# ZynqPSDDR.net
KiCad netlist of a schematic drawn in Altium Designer
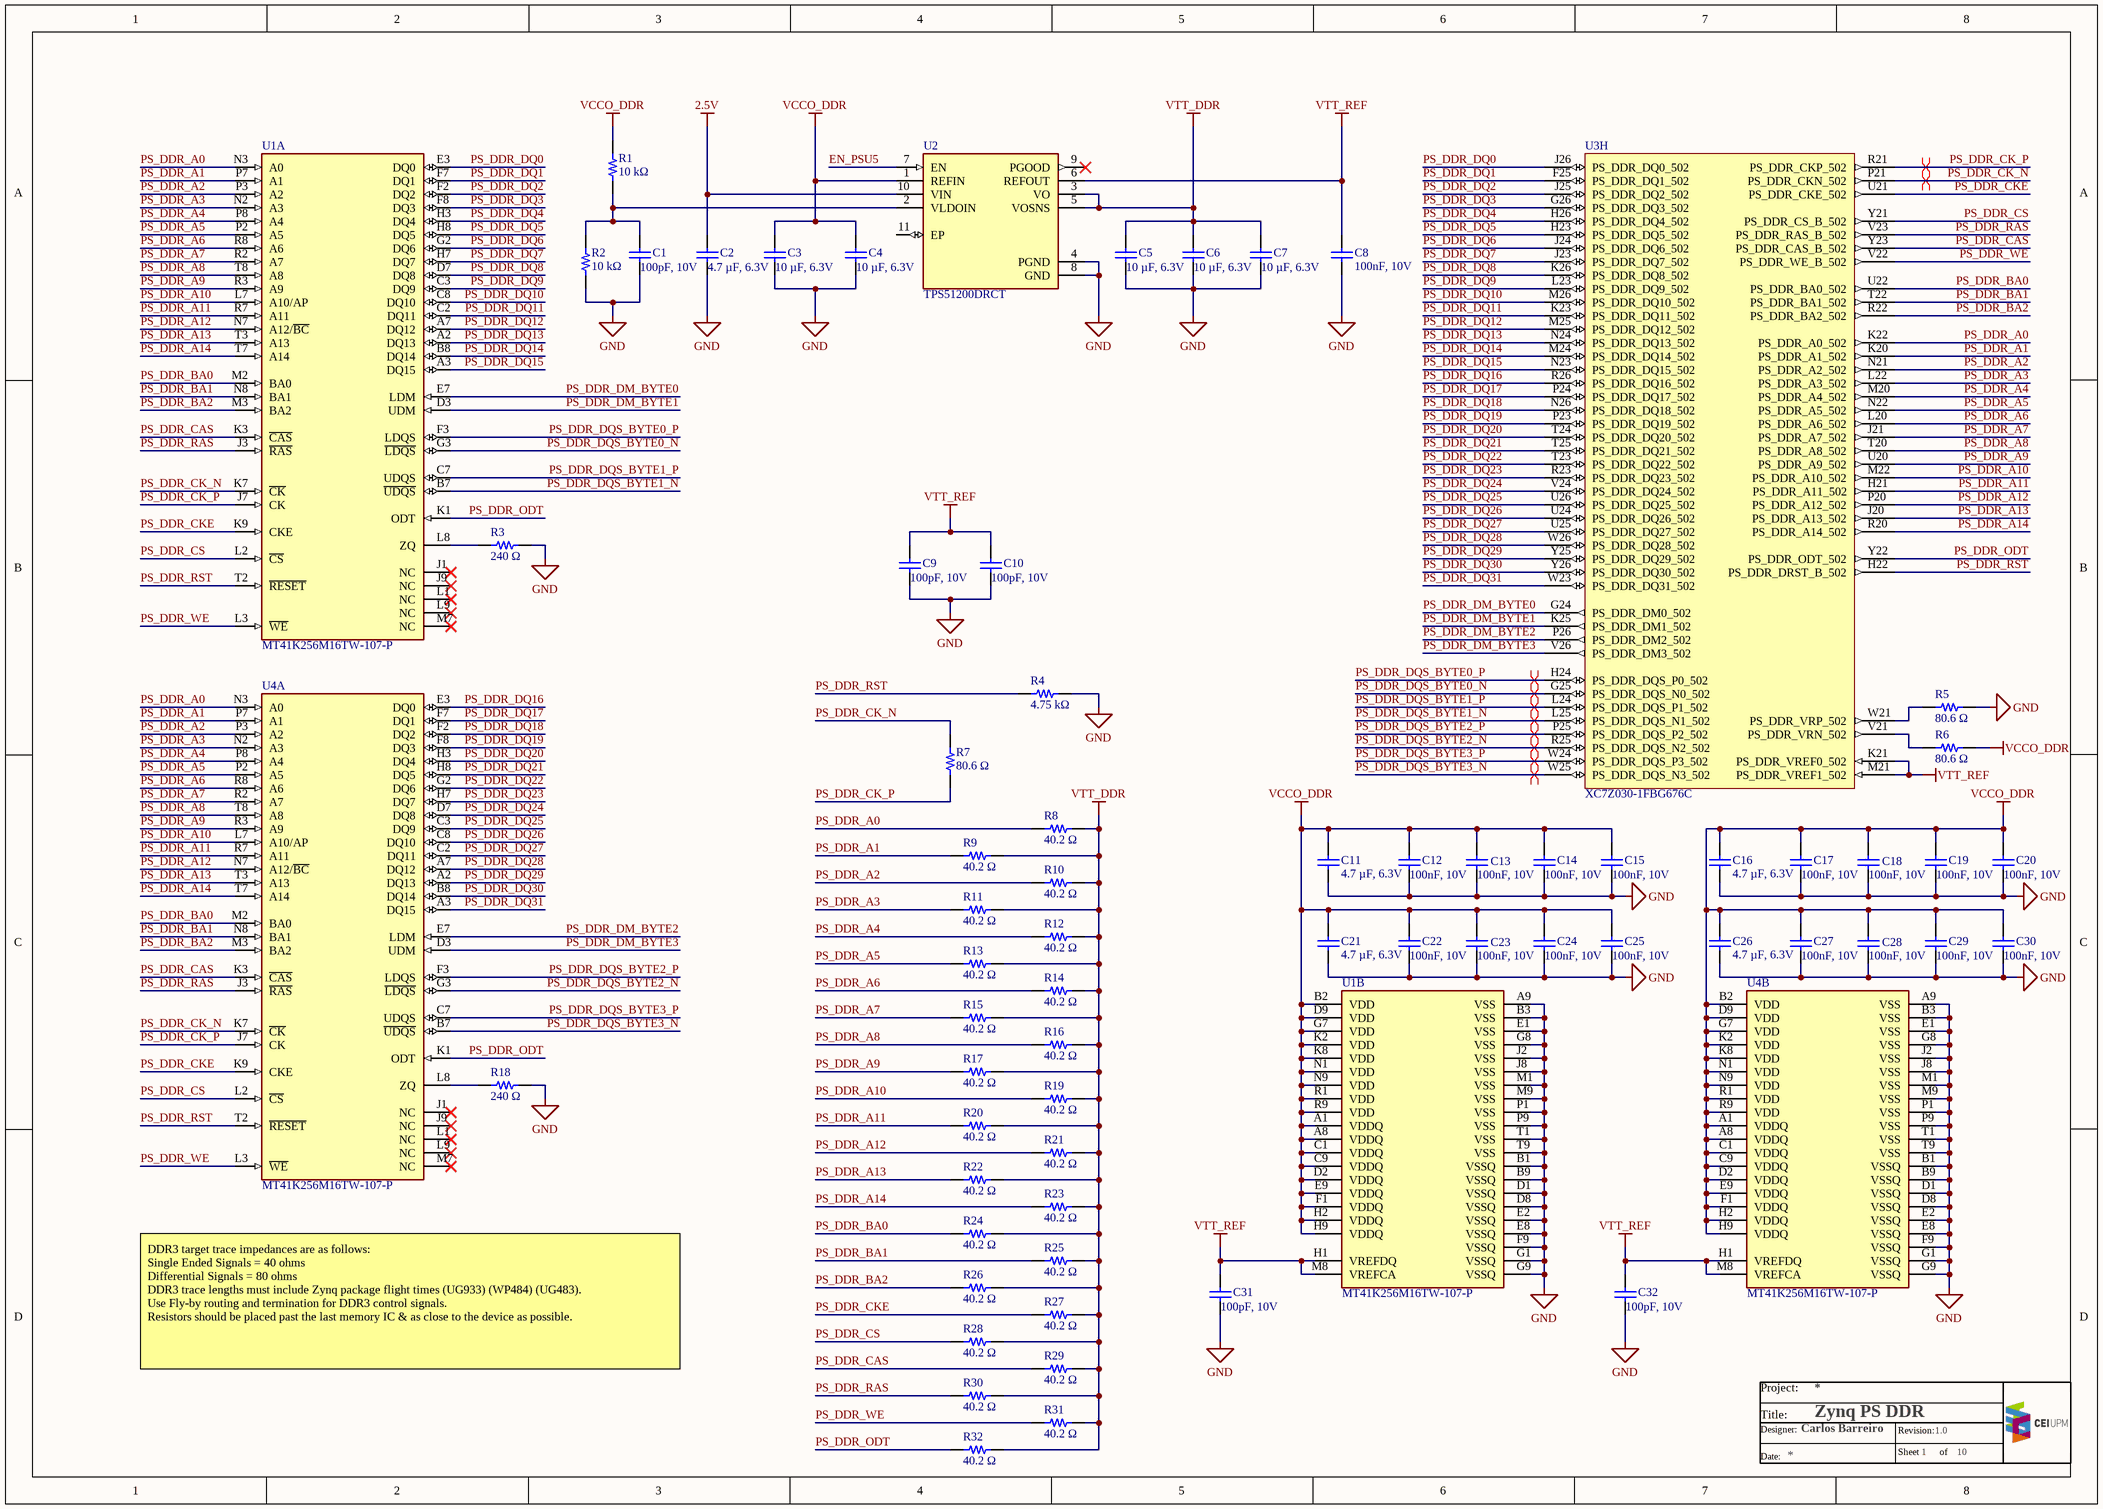
[diagram p0: ZynqPSDDR.SchDoc]

(export (version "E")
  (design (tool "Eeschema 10.0.6"))
  (components
    (comp (ref "C1")
      (value "100pF, 10V")
      (footprint "WURTH_WCAP-CSGP_0402")
      (description "WCAP-CSGP Multilayer Ceramic Chip Capacitor, General Purpose, size 0402, NP0, 100pF, 10V")
      (fields
        (field (name "MANUFACTURER PART NUMBER") "885012005013")
        (field (name "MANUFACTURER") "Wurth Elektronik")
      )
      (libsource (lib "SpaceVNXBaseBoard") (part "885012005013"))
    )
    (comp (ref "C2")
      (value "4.7 µF, 6.3V")
      (footprint "WURTH_WCAP-CSGP_0402")
      (description "Multilayer Ceramic Capacitors MLCC, size 0402, X5R, 4.7 µF, 6.3V")
      (fields
        (field (name "MANUFACTURER PART NUMBER") "GRM155C80J475MEAAD")
        (field (name "MANUFACTURER") "Murata")
      )
      (libsource (lib "SpaceVNXBaseBoard") (part "GRM155C80J475MEAAD"))
    )
    (comp (ref "C3")
      (value "10 µF, 6.3V")
      (footprint "WURTH_WCAP-CSGP_0402")
      (description "WCAP-CSGP Multilayer Ceramic Chip Capacitor, General Purpose, size 0402, X5R, 10uF, 6.3V")
      (fields
        (field (name "MANUFACTURER PART NUMBER") "885012105020")
        (field (name "MANUFACTURER") "Wurth Elektronik")
      )
      (libsource (lib "SpaceVNXBaseBoard") (part "885012105020"))
    )
    (comp (ref "C4")
      (value "10 µF, 6.3V")
      (footprint "WURTH_WCAP-CSGP_0402")
      (description "WCAP-CSGP Multilayer Ceramic Chip Capacitor, General Purpose, size 0402, X5R, 10uF, 6.3V")
      (fields
        (field (name "MANUFACTURER PART NUMBER") "885012105020")
        (field (name "MANUFACTURER") "Wurth Elektronik")
      )
      (libsource (lib "SpaceVNXBaseBoard") (part "885012105020"))
    )
    (comp (ref "C5")
      (value "10 µF, 6.3V")
      (footprint "WURTH_WCAP-CSGP_0402")
      (description "WCAP-CSGP Multilayer Ceramic Chip Capacitor, General Purpose, size 0402, X5R, 10uF, 6.3V")
      (fields
        (field (name "MANUFACTURER PART NUMBER") "885012105020")
        (field (name "MANUFACTURER") "Wurth Elektronik")
      )
      (libsource (lib "SpaceVNXBaseBoard") (part "885012105020"))
    )
    (comp (ref "C6")
      (value "10 µF, 6.3V")
      (footprint "WURTH_WCAP-CSGP_0402")
      (description "WCAP-CSGP Multilayer Ceramic Chip Capacitor, General Purpose, size 0402, X5R, 10uF, 6.3V")
      (fields
        (field (name "MANUFACTURER PART NUMBER") "885012105020")
        (field (name "MANUFACTURER") "Wurth Elektronik")
      )
      (libsource (lib "SpaceVNXBaseBoard") (part "885012105020"))
    )
    (comp (ref "C7")
      (value "10 µF, 6.3V")
      (footprint "WURTH_WCAP-CSGP_0402")
      (description "WCAP-CSGP Multilayer Ceramic Chip Capacitor, General Purpose, size 0402, X5R, 10uF, 6.3V")
      (fields
        (field (name "MANUFACTURER PART NUMBER") "885012105020")
        (field (name "MANUFACTURER") "Wurth Elektronik")
      )
      (libsource (lib "SpaceVNXBaseBoard") (part "885012105020"))
    )
    (comp (ref "C8")
      (value "100nF, 10V")
      (footprint "WURTH_WCAP-CSGP_0402")
      (description "WCAP-CSGP Multilayer Ceramic Chip Capacitor, General Purpose, size 0402, X7R, 100nF, 10V")
      (fields
        (field (name "MANUFACTURER PART NUMBER") "885012205018")
        (field (name "MANUFACTURER") "Wurth Elektronik")
      )
      (libsource (lib "SpaceVNXBaseBoard") (part "885012205018"))
    )
    (comp (ref "C9")
      (value "100pF, 10V")
      (footprint "WURTH_WCAP-CSGP_0402")
      (description "WCAP-CSGP Multilayer Ceramic Chip Capacitor, General Purpose, size 0402, NP0, 100pF, 10V")
      (fields
        (field (name "MANUFACTURER PART NUMBER") "885012005013")
        (field (name "MANUFACTURER") "Wurth Elektronik")
      )
      (libsource (lib "SpaceVNXBaseBoard") (part "885012005013"))
    )
    (comp (ref "C10")
      (value "100pF, 10V")
      (footprint "WURTH_WCAP-CSGP_0402")
      (description "WCAP-CSGP Multilayer Ceramic Chip Capacitor, General Purpose, size 0402, NP0, 100pF, 10V")
      (fields
        (field (name "MANUFACTURER PART NUMBER") "885012005013")
        (field (name "MANUFACTURER") "Wurth Elektronik")
      )
      (libsource (lib "SpaceVNXBaseBoard") (part "885012005013"))
    )
    (comp (ref "C11")
      (value "4.7 µF, 6.3V")
      (footprint "WURTH_WCAP-CSGP_0402")
      (description "Multilayer Ceramic Capacitors MLCC, size 0402, X5R, 4.7 µF, 6.3V")
      (fields
        (field (name "MANUFACTURER PART NUMBER") "GRM155C80J475MEAAD")
        (field (name "MANUFACTURER") "Murata")
      )
      (libsource (lib "SpaceVNXBaseBoard") (part "GRM155C80J475MEAAD"))
    )
    (comp (ref "C12")
      (value "100nF, 10V")
      (footprint "WURTH_WCAP-CSGP_0402")
      (description "WCAP-CSGP Multilayer Ceramic Chip Capacitor, General Purpose, size 0402, X7R, 100nF, 10V")
      (fields
        (field (name "MANUFACTURER PART NUMBER") "885012205018")
        (field (name "MANUFACTURER") "Wurth Elektronik")
      )
      (libsource (lib "SpaceVNXBaseBoard") (part "885012205018"))
    )
    (comp (ref "C13")
      (value "100nF, 10V")
      (footprint "WURTH_WCAP-CSGP_0402")
      (description "WCAP-CSGP Multilayer Ceramic Chip Capacitor, General Purpose, size 0402, X7R, 100nF, 10V")
      (fields
        (field (name "MANUFACTURER PART NUMBER") "885012205018")
        (field (name "MANUFACTURER") "Wurth Elektronik")
      )
      (libsource (lib "SpaceVNXBaseBoard") (part "885012205018"))
    )
    (comp (ref "C14")
      (value "100nF, 10V")
      (footprint "WURTH_WCAP-CSGP_0402")
      (description "WCAP-CSGP Multilayer Ceramic Chip Capacitor, General Purpose, size 0402, X7R, 100nF, 10V")
      (fields
        (field (name "MANUFACTURER PART NUMBER") "885012205018")
        (field (name "MANUFACTURER") "Wurth Elektronik")
      )
      (libsource (lib "SpaceVNXBaseBoard") (part "885012205018"))
    )
    (comp (ref "C15")
      (value "100nF, 10V")
      (footprint "WURTH_WCAP-CSGP_0402")
      (description "WCAP-CSGP Multilayer Ceramic Chip Capacitor, General Purpose, size 0402, X7R, 100nF, 10V")
      (fields
        (field (name "MANUFACTURER PART NUMBER") "885012205018")
        (field (name "MANUFACTURER") "Wurth Elektronik")
      )
      (libsource (lib "SpaceVNXBaseBoard") (part "885012205018"))
    )
    (comp (ref "C16")
      (value "4.7 µF, 6.3V")
      (footprint "WURTH_WCAP-CSGP_0402")
      (description "Multilayer Ceramic Capacitors MLCC, size 0402, X5R, 4.7 µF, 6.3V")
      (fields
        (field (name "MANUFACTURER PART NUMBER") "GRM155C80J475MEAAD")
        (field (name "MANUFACTURER") "Murata")
      )
      (libsource (lib "SpaceVNXBaseBoard") (part "GRM155C80J475MEAAD"))
    )
    (comp (ref "C17")
      (value "100nF, 10V")
      (footprint "WURTH_WCAP-CSGP_0402")
      (description "WCAP-CSGP Multilayer Ceramic Chip Capacitor, General Purpose, size 0402, X7R, 100nF, 10V")
      (fields
        (field (name "MANUFACTURER PART NUMBER") "885012205018")
        (field (name "MANUFACTURER") "Wurth Elektronik")
      )
      (libsource (lib "SpaceVNXBaseBoard") (part "885012205018"))
    )
    (comp (ref "C18")
      (value "100nF, 10V")
      (footprint "WURTH_WCAP-CSGP_0402")
      (description "WCAP-CSGP Multilayer Ceramic Chip Capacitor, General Purpose, size 0402, X7R, 100nF, 10V")
      (fields
        (field (name "MANUFACTURER PART NUMBER") "885012205018")
        (field (name "MANUFACTURER") "Wurth Elektronik")
      )
      (libsource (lib "SpaceVNXBaseBoard") (part "885012205018"))
    )
    (comp (ref "C19")
      (value "100nF, 10V")
      (footprint "WURTH_WCAP-CSGP_0402")
      (description "WCAP-CSGP Multilayer Ceramic Chip Capacitor, General Purpose, size 0402, X7R, 100nF, 10V")
      (fields
        (field (name "MANUFACTURER PART NUMBER") "885012205018")
        (field (name "MANUFACTURER") "Wurth Elektronik")
      )
      (libsource (lib "SpaceVNXBaseBoard") (part "885012205018"))
    )
    (comp (ref "C20")
      (value "100nF, 10V")
      (footprint "WURTH_WCAP-CSGP_0402")
      (description "WCAP-CSGP Multilayer Ceramic Chip Capacitor, General Purpose, size 0402, X7R, 100nF, 10V")
      (fields
        (field (name "MANUFACTURER PART NUMBER") "885012205018")
        (field (name "MANUFACTURER") "Wurth Elektronik")
      )
      (libsource (lib "SpaceVNXBaseBoard") (part "885012205018"))
    )
    (comp (ref "C21")
      (value "4.7 µF, 6.3V")
      (footprint "WURTH_WCAP-CSGP_0402")
      (description "Multilayer Ceramic Capacitors MLCC, size 0402, X5R, 4.7 µF, 6.3V")
      (fields
        (field (name "MANUFACTURER PART NUMBER") "GRM155C80J475MEAAD")
        (field (name "MANUFACTURER") "Murata")
      )
      (libsource (lib "SpaceVNXBaseBoard") (part "GRM155C80J475MEAAD"))
    )
    (comp (ref "C22")
      (value "100nF, 10V")
      (footprint "WURTH_WCAP-CSGP_0402")
      (description "WCAP-CSGP Multilayer Ceramic Chip Capacitor, General Purpose, size 0402, X7R, 100nF, 10V")
      (fields
        (field (name "MANUFACTURER PART NUMBER") "885012205018")
        (field (name "MANUFACTURER") "Wurth Elektronik")
      )
      (libsource (lib "SpaceVNXBaseBoard") (part "885012205018"))
    )
    (comp (ref "C23")
      (value "100nF, 10V")
      (footprint "WURTH_WCAP-CSGP_0402")
      (description "WCAP-CSGP Multilayer Ceramic Chip Capacitor, General Purpose, size 0402, X7R, 100nF, 10V")
      (fields
        (field (name "MANUFACTURER PART NUMBER") "885012205018")
        (field (name "MANUFACTURER") "Wurth Elektronik")
      )
      (libsource (lib "SpaceVNXBaseBoard") (part "885012205018"))
    )
    (comp (ref "C24")
      (value "100nF, 10V")
      (footprint "WURTH_WCAP-CSGP_0402")
      (description "WCAP-CSGP Multilayer Ceramic Chip Capacitor, General Purpose, size 0402, X7R, 100nF, 10V")
      (fields
        (field (name "MANUFACTURER PART NUMBER") "885012205018")
        (field (name "MANUFACTURER") "Wurth Elektronik")
      )
      (libsource (lib "SpaceVNXBaseBoard") (part "885012205018"))
    )
    (comp (ref "C25")
      (value "100nF, 10V")
      (footprint "WURTH_WCAP-CSGP_0402")
      (description "WCAP-CSGP Multilayer Ceramic Chip Capacitor, General Purpose, size 0402, X7R, 100nF, 10V")
      (fields
        (field (name "MANUFACTURER PART NUMBER") "885012205018")
        (field (name "MANUFACTURER") "Wurth Elektronik")
      )
      (libsource (lib "SpaceVNXBaseBoard") (part "885012205018"))
    )
    (comp (ref "C26")
      (value "4.7 µF, 6.3V")
      (footprint "WURTH_WCAP-CSGP_0402")
      (description "Multilayer Ceramic Capacitors MLCC, size 0402, X5R, 4.7 µF, 6.3V")
      (fields
        (field (name "MANUFACTURER PART NUMBER") "GRM155C80J475MEAAD")
        (field (name "MANUFACTURER") "Murata")
      )
      (libsource (lib "SpaceVNXBaseBoard") (part "GRM155C80J475MEAAD"))
    )
    (comp (ref "C27")
      (value "100nF, 10V")
      (footprint "WURTH_WCAP-CSGP_0402")
      (description "WCAP-CSGP Multilayer Ceramic Chip Capacitor, General Purpose, size 0402, X7R, 100nF, 10V")
      (fields
        (field (name "MANUFACTURER PART NUMBER") "885012205018")
        (field (name "MANUFACTURER") "Wurth Elektronik")
      )
      (libsource (lib "SpaceVNXBaseBoard") (part "885012205018"))
    )
    (comp (ref "C28")
      (value "100nF, 10V")
      (footprint "WURTH_WCAP-CSGP_0402")
      (description "WCAP-CSGP Multilayer Ceramic Chip Capacitor, General Purpose, size 0402, X7R, 100nF, 10V")
      (fields
        (field (name "MANUFACTURER PART NUMBER") "885012205018")
        (field (name "MANUFACTURER") "Wurth Elektronik")
      )
      (libsource (lib "SpaceVNXBaseBoard") (part "885012205018"))
    )
    (comp (ref "C29")
      (value "100nF, 10V")
      (footprint "WURTH_WCAP-CSGP_0402")
      (description "WCAP-CSGP Multilayer Ceramic Chip Capacitor, General Purpose, size 0402, X7R, 100nF, 10V")
      (fields
        (field (name "MANUFACTURER PART NUMBER") "885012205018")
        (field (name "MANUFACTURER") "Wurth Elektronik")
      )
      (libsource (lib "SpaceVNXBaseBoard") (part "885012205018"))
    )
    (comp (ref "C30")
      (value "100nF, 10V")
      (footprint "WURTH_WCAP-CSGP_0402")
      (description "WCAP-CSGP Multilayer Ceramic Chip Capacitor, General Purpose, size 0402, X7R, 100nF, 10V")
      (fields
        (field (name "MANUFACTURER PART NUMBER") "885012205018")
        (field (name "MANUFACTURER") "Wurth Elektronik")
      )
      (libsource (lib "SpaceVNXBaseBoard") (part "885012205018"))
    )
    (comp (ref "C31")
      (value "100pF, 10V")
      (footprint "WURTH_WCAP-CSGP_0402")
      (description "WCAP-CSGP Multilayer Ceramic Chip Capacitor, General Purpose, size 0402, NP0, 100pF, 10V")
      (fields
        (field (name "MANUFACTURER PART NUMBER") "885012005013")
        (field (name "MANUFACTURER") "Wurth Elektronik")
      )
      (libsource (lib "SpaceVNXBaseBoard") (part "885012005013"))
    )
    (comp (ref "C32")
      (value "100pF, 10V")
      (footprint "WURTH_WCAP-CSGP_0402")
      (description "WCAP-CSGP Multilayer Ceramic Chip Capacitor, General Purpose, size 0402, NP0, 100pF, 10V")
      (fields
        (field (name "MANUFACTURER PART NUMBER") "885012005013")
        (field (name "MANUFACTURER") "Wurth Elektronik")
      )
      (libsource (lib "SpaceVNXBaseBoard") (part "885012005013"))
    )
    (comp (ref "R1")
      (value "10 kΩ")
      (footprint "PANASONIC_ERJ2G_0402")
      (description "General Purpose Thick Film Chip Resistors")
      (fields (field (name "MANUFACTURER") "Panasonic"))
      (libsource (lib "SpaceVNXBaseBoard") (part "ERJ2RKF1002X"))
    )
    (comp (ref "R2")
      (value "10 kΩ")
      (footprint "PANASONIC_ERJ2G_0402")
      (description "General Purpose Thick Film Chip Resistors")
      (fields (field (name "MANUFACTURER") "Panasonic"))
      (libsource (lib "SpaceVNXBaseBoard") (part "ERJ2RKF1002X"))
    )
    (comp (ref "R3")
      (value "240 Ω")
      (footprint "PANASONIC_ERJ2G_0402")
      (description "General Purpose Thick Film Chip Resistors")
      (fields (field (name "MANUFACTURER") "Panasonic"))
      (libsource (lib "SpaceVNXBaseBoard") (part "ERJ2GEJ241X"))
    )
    (comp (ref "R4")
      (value "4.75 kΩ")
      (footprint "PANASONIC_ERJ2G_0402")
      (description "General Purpose Thick Film Chip Resistors")
      (fields (field (name "MANUFACTURER") "Panasonic"))
      (libsource (lib "SpaceVNXBaseBoard") (part "ERJ2RKF4751X"))
    )
    (comp (ref "R5")
      (value "80.6 Ω")
      (footprint "PANASONIC_ERJ2G_0402")
      (description "General Purpose Thick Film Chip Resistors")
      (fields (field (name "MANUFACTURER") "Panasonic"))
      (libsource (lib "SpaceVNXBaseBoard") (part "ERJ2RKF80R6X"))
    )
    (comp (ref "R6")
      (value "80.6 Ω")
      (footprint "PANASONIC_ERJ2G_0402")
      (description "General Purpose Thick Film Chip Resistors")
      (fields (field (name "MANUFACTURER") "Panasonic"))
      (libsource (lib "SpaceVNXBaseBoard") (part "ERJ2RKF80R6X"))
    )
    (comp (ref "R7")
      (value "80.6 Ω")
      (footprint "PANASONIC_ERJ2G_0402")
      (description "General Purpose Thick Film Chip Resistors")
      (fields (field (name "MANUFACTURER") "Panasonic"))
      (libsource (lib "SpaceVNXBaseBoard") (part "ERJ2RKF80R6X"))
    )
    (comp (ref "R8")
      (value "40.2 Ω")
      (footprint "PANASONIC_ERJ2G_0402")
      (description "General Purpose Thick Film Chip Resistors")
      (fields (field (name "MANUFACTURER") "Panasonic"))
      (libsource (lib "SpaceVNXBaseBoard") (part "ERJ2RKF40R2X"))
    )
    (comp (ref "R9")
      (value "40.2 Ω")
      (footprint "PANASONIC_ERJ2G_0402")
      (description "General Purpose Thick Film Chip Resistors")
      (fields (field (name "MANUFACTURER") "Panasonic"))
      (libsource (lib "SpaceVNXBaseBoard") (part "ERJ2RKF40R2X"))
    )
    (comp (ref "R10")
      (value "40.2 Ω")
      (footprint "PANASONIC_ERJ2G_0402")
      (description "General Purpose Thick Film Chip Resistors")
      (fields (field (name "MANUFACTURER") "Panasonic"))
      (libsource (lib "SpaceVNXBaseBoard") (part "ERJ2RKF40R2X"))
    )
    (comp (ref "R11")
      (value "40.2 Ω")
      (footprint "PANASONIC_ERJ2G_0402")
      (description "General Purpose Thick Film Chip Resistors")
      (fields (field (name "MANUFACTURER") "Panasonic"))
      (libsource (lib "SpaceVNXBaseBoard") (part "ERJ2RKF40R2X"))
    )
    (comp (ref "R12")
      (value "40.2 Ω")
      (footprint "PANASONIC_ERJ2G_0402")
      (description "General Purpose Thick Film Chip Resistors")
      (fields (field (name "MANUFACTURER") "Panasonic"))
      (libsource (lib "SpaceVNXBaseBoard") (part "ERJ2RKF40R2X"))
    )
    (comp (ref "R13")
      (value "40.2 Ω")
      (footprint "PANASONIC_ERJ2G_0402")
      (description "General Purpose Thick Film Chip Resistors")
      (fields (field (name "MANUFACTURER") "Panasonic"))
      (libsource (lib "SpaceVNXBaseBoard") (part "ERJ2RKF40R2X"))
    )
    (comp (ref "R14")
      (value "40.2 Ω")
      (footprint "PANASONIC_ERJ2G_0402")
      (description "General Purpose Thick Film Chip Resistors")
      (fields (field (name "MANUFACTURER") "Panasonic"))
      (libsource (lib "SpaceVNXBaseBoard") (part "ERJ2RKF40R2X"))
    )
    (comp (ref "R15")
      (value "40.2 Ω")
      (footprint "PANASONIC_ERJ2G_0402")
      (description "General Purpose Thick Film Chip Resistors")
      (fields (field (name "MANUFACTURER") "Panasonic"))
      (libsource (lib "SpaceVNXBaseBoard") (part "ERJ2RKF40R2X"))
    )
    (comp (ref "R16")
      (value "40.2 Ω")
      (footprint "PANASONIC_ERJ2G_0402")
      (description "General Purpose Thick Film Chip Resistors")
      (fields (field (name "MANUFACTURER") "Panasonic"))
      (libsource (lib "SpaceVNXBaseBoard") (part "ERJ2RKF40R2X"))
    )
    (comp (ref "R17")
      (value "40.2 Ω")
      (footprint "PANASONIC_ERJ2G_0402")
      (description "General Purpose Thick Film Chip Resistors")
      (fields (field (name "MANUFACTURER") "Panasonic"))
      (libsource (lib "SpaceVNXBaseBoard") (part "ERJ2RKF40R2X"))
    )
    (comp (ref "R18")
      (value "240 Ω")
      (footprint "PANASONIC_ERJ2G_0402")
      (description "General Purpose Thick Film Chip Resistors")
      (fields (field (name "MANUFACTURER") "Panasonic"))
      (libsource (lib "SpaceVNXBaseBoard") (part "ERJ2GEJ241X"))
    )
    (comp (ref "R19")
      (value "40.2 Ω")
      (footprint "PANASONIC_ERJ2G_0402")
      (description "General Purpose Thick Film Chip Resistors")
      (fields (field (name "MANUFACTURER") "Panasonic"))
      (libsource (lib "SpaceVNXBaseBoard") (part "ERJ2RKF40R2X"))
    )
    (comp (ref "R20")
      (value "40.2 Ω")
      (footprint "PANASONIC_ERJ2G_0402")
      (description "General Purpose Thick Film Chip Resistors")
      (fields (field (name "MANUFACTURER") "Panasonic"))
      (libsource (lib "SpaceVNXBaseBoard") (part "ERJ2RKF40R2X"))
    )
    (comp (ref "R21")
      (value "40.2 Ω")
      (footprint "PANASONIC_ERJ2G_0402")
      (description "General Purpose Thick Film Chip Resistors")
      (fields (field (name "MANUFACTURER") "Panasonic"))
      (libsource (lib "SpaceVNXBaseBoard") (part "ERJ2RKF40R2X"))
    )
    (comp (ref "R22")
      (value "40.2 Ω")
      (footprint "PANASONIC_ERJ2G_0402")
      (description "General Purpose Thick Film Chip Resistors")
      (fields (field (name "MANUFACTURER") "Panasonic"))
      (libsource (lib "SpaceVNXBaseBoard") (part "ERJ2RKF40R2X"))
    )
    (comp (ref "R23")
      (value "40.2 Ω")
      (footprint "PANASONIC_ERJ2G_0402")
      (description "General Purpose Thick Film Chip Resistors")
      (fields (field (name "MANUFACTURER") "Panasonic"))
      (libsource (lib "SpaceVNXBaseBoard") (part "ERJ2RKF40R2X"))
    )
    (comp (ref "R24")
      (value "40.2 Ω")
      (footprint "PANASONIC_ERJ2G_0402")
      (description "General Purpose Thick Film Chip Resistors")
      (fields (field (name "MANUFACTURER") "Panasonic"))
      (libsource (lib "SpaceVNXBaseBoard") (part "ERJ2RKF40R2X"))
    )
    (comp (ref "R25")
      (value "40.2 Ω")
      (footprint "PANASONIC_ERJ2G_0402")
      (description "General Purpose Thick Film Chip Resistors")
      (fields (field (name "MANUFACTURER") "Panasonic"))
      (libsource (lib "SpaceVNXBaseBoard") (part "ERJ2RKF40R2X"))
    )
    (comp (ref "R26")
      (value "40.2 Ω")
      (footprint "PANASONIC_ERJ2G_0402")
      (description "General Purpose Thick Film Chip Resistors")
      (fields (field (name "MANUFACTURER") "Panasonic"))
      (libsource (lib "SpaceVNXBaseBoard") (part "ERJ2RKF40R2X"))
    )
    (comp (ref "R27")
      (value "40.2 Ω")
      (footprint "PANASONIC_ERJ2G_0402")
      (description "General Purpose Thick Film Chip Resistors")
      (fields (field (name "MANUFACTURER") "Panasonic"))
      (libsource (lib "SpaceVNXBaseBoard") (part "ERJ2RKF40R2X"))
    )
    (comp (ref "R28")
      (value "40.2 Ω")
      (footprint "PANASONIC_ERJ2G_0402")
      (description "General Purpose Thick Film Chip Resistors")
      (fields (field (name "MANUFACTURER") "Panasonic"))
      (libsource (lib "SpaceVNXBaseBoard") (part "ERJ2RKF40R2X"))
    )
    (comp (ref "R29")
      (value "40.2 Ω")
      (footprint "PANASONIC_ERJ2G_0402")
      (description "General Purpose Thick Film Chip Resistors")
      (fields (field (name "MANUFACTURER") "Panasonic"))
      (libsource (lib "SpaceVNXBaseBoard") (part "ERJ2RKF40R2X"))
    )
    (comp (ref "R30")
      (value "40.2 Ω")
      (footprint "PANASONIC_ERJ2G_0402")
      (description "General Purpose Thick Film Chip Resistors")
      (fields (field (name "MANUFACTURER") "Panasonic"))
      (libsource (lib "SpaceVNXBaseBoard") (part "ERJ2RKF40R2X"))
    )
    (comp (ref "R31")
      (value "40.2 Ω")
      (footprint "PANASONIC_ERJ2G_0402")
      (description "General Purpose Thick Film Chip Resistors")
      (fields (field (name "MANUFACTURER") "Panasonic"))
      (libsource (lib "SpaceVNXBaseBoard") (part "ERJ2RKF40R2X"))
    )
    (comp (ref "R32")
      (value "40.2 Ω")
      (footprint "PANASONIC_ERJ2G_0402")
      (description "General Purpose Thick Film Chip Resistors")
      (fields (field (name "MANUFACTURER") "Panasonic"))
      (libsource (lib "SpaceVNXBaseBoard") (part "ERJ2RKF40R2X"))
    )
    (comp (ref "U1")
      (value "MT41K256M16TW-107-P")
      (footprint "Micron_TW")
      (description "DDR3L SRAM 256Mb*16")
      (libsource (lib "SpaceVNXBaseBoard") (part "MT41K256M16TW-107-P"))
    )
    (comp (ref "U2")
      (value "TPS51200DRCT")
      (footprint "TEXAS_VSON10")
      (fields (field (name "MF") "Texas Instruments"))
      (libsource (lib "SpaceVNXBaseBoard") (part "TPS51200DRCT"))
    )
    (comp (ref "U3")
      (value "XC7Z030-1FBG676C")
      (footprint "XILINX_FBG676")
      (fields (field (name "GENERIC PART NUMBER") "XC7Z030"))
      (libsource (lib "SpaceVNXBaseBoard") (part "XC7Z030-1FBG676C"))
    )
    (comp (ref "U4")
      (value "MT41K256M16TW-107-P")
      (footprint "Micron_TW")
      (description "DDR3L SRAM 256Mb*16")
      (libsource (lib "SpaceVNXBaseBoard") (part "MT41K256M16TW-107-P"))
    )
  )
  (nets
    (net (code "1") (name "/EN_PSU5") (class "Default")
      (node (ref "U2") (pin "7") (pinfunction "EN_7") (pintype "input"))
    )
    (net (code "2") (name "/PS_DDR_A0") (class "Default")
      (node (ref "R8") (pin "1") (pinfunction "1_1") (pintype "passive"))
      (node (ref "U1") (pin "N3") (pinfunction "A0_N3") (pintype "input"))
      (node (ref "U3") (pin "K22") (pinfunction "PS_DDR_A0_502_K22") (pintype "output"))
      (node (ref "U4") (pin "N3") (pinfunction "A0_N3") (pintype "input"))
    )
    (net (code "3") (name "/PS_DDR_A1") (class "Default")
      (node (ref "R9") (pin "1") (pinfunction "1_1") (pintype "passive"))
      (node (ref "U1") (pin "P7") (pinfunction "A1_P7") (pintype "input"))
      (node (ref "U3") (pin "K20") (pinfunction "PS_DDR_A1_502_K20") (pintype "output"))
      (node (ref "U4") (pin "P7") (pinfunction "A1_P7") (pintype "input"))
    )
    (net (code "4") (name "/PS_DDR_A2") (class "Default")
      (node (ref "R10") (pin "1") (pinfunction "1_1") (pintype "passive"))
      (node (ref "U1") (pin "P3") (pinfunction "A2_P3") (pintype "input"))
      (node (ref "U3") (pin "N21") (pinfunction "PS_DDR_A2_502_N21") (pintype "output"))
      (node (ref "U4") (pin "P3") (pinfunction "A2_P3") (pintype "input"))
    )
    (net (code "5") (name "/PS_DDR_A3") (class "Default")
      (node (ref "R11") (pin "1") (pinfunction "1_1") (pintype "passive"))
      (node (ref "U1") (pin "N2") (pinfunction "A3_N2") (pintype "input"))
      (node (ref "U3") (pin "L22") (pinfunction "PS_DDR_A3_502_L22") (pintype "output"))
      (node (ref "U4") (pin "N2") (pinfunction "A3_N2") (pintype "input"))
    )
    (net (code "6") (name "/PS_DDR_A4") (class "Default")
      (node (ref "R12") (pin "1") (pinfunction "1_1") (pintype "passive"))
      (node (ref "U1") (pin "P8") (pinfunction "A4_P8") (pintype "input"))
      (node (ref "U3") (pin "M20") (pinfunction "PS_DDR_A4_502_M20") (pintype "output"))
      (node (ref "U4") (pin "P8") (pinfunction "A4_P8") (pintype "input"))
    )
    (net (code "7") (name "/PS_DDR_A5") (class "Default")
      (node (ref "R13") (pin "1") (pinfunction "1_1") (pintype "passive"))
      (node (ref "U1") (pin "P2") (pinfunction "A5_P2") (pintype "input"))
      (node (ref "U3") (pin "N22") (pinfunction "PS_DDR_A5_502_N22") (pintype "output"))
      (node (ref "U4") (pin "P2") (pinfunction "A5_P2") (pintype "input"))
    )
    (net (code "8") (name "/PS_DDR_A6") (class "Default")
      (node (ref "R14") (pin "1") (pinfunction "1_1") (pintype "passive"))
      (node (ref "U1") (pin "R8") (pinfunction "A6_R8") (pintype "input"))
      (node (ref "U3") (pin "L20") (pinfunction "PS_DDR_A6_502_L20") (pintype "output"))
      (node (ref "U4") (pin "R8") (pinfunction "A6_R8") (pintype "input"))
    )
    (net (code "9") (name "/PS_DDR_A7") (class "Default")
      (node (ref "R15") (pin "1") (pinfunction "1_1") (pintype "passive"))
      (node (ref "U1") (pin "R2") (pinfunction "A7_R2") (pintype "input"))
      (node (ref "U3") (pin "J21") (pinfunction "PS_DDR_A7_502_J21") (pintype "output"))
      (node (ref "U4") (pin "R2") (pinfunction "A7_R2") (pintype "input"))
    )
    (net (code "10") (name "/PS_DDR_A8") (class "Default")
      (node (ref "R16") (pin "1") (pinfunction "1_1") (pintype "passive"))
      (node (ref "U1") (pin "T8") (pinfunction "A8_T8") (pintype "input"))
      (node (ref "U3") (pin "T20") (pinfunction "PS_DDR_A8_502_T20") (pintype "output"))
      (node (ref "U4") (pin "T8") (pinfunction "A8_T8") (pintype "input"))
    )
    (net (code "11") (name "/PS_DDR_A9") (class "Default")
      (node (ref "R17") (pin "1") (pinfunction "1_1") (pintype "passive"))
      (node (ref "U1") (pin "R3") (pinfunction "A9_R3") (pintype "input"))
      (node (ref "U3") (pin "U20") (pinfunction "PS_DDR_A9_502_U20") (pintype "output"))
      (node (ref "U4") (pin "R3") (pinfunction "A9_R3") (pintype "input"))
    )
    (net (code "12") (name "/PS_DDR_A10") (class "Default")
      (node (ref "R19") (pin "1") (pinfunction "1_1") (pintype "passive"))
      (node (ref "U1") (pin "L7") (pinfunction "A10/AP_L7") (pintype "input"))
      (node (ref "U3") (pin "M22") (pinfunction "PS_DDR_A10_502_M22") (pintype "output"))
      (node (ref "U4") (pin "L7") (pinfunction "A10/AP_L7") (pintype "input"))
    )
    (net (code "13") (name "/PS_DDR_A11") (class "Default")
      (node (ref "R20") (pin "1") (pinfunction "1_1") (pintype "passive"))
      (node (ref "U1") (pin "R7") (pinfunction "A11_R7") (pintype "input"))
      (node (ref "U3") (pin "H21") (pinfunction "PS_DDR_A11_502_H21") (pintype "output"))
      (node (ref "U4") (pin "R7") (pinfunction "A11_R7") (pintype "input"))
    )
    (net (code "14") (name "/PS_DDR_A12") (class "Default")
      (node (ref "R21") (pin "1") (pinfunction "1_1") (pintype "passive"))
      (node (ref "U1") (pin "N7") (pinfunction "A12/~{BC}_N7") (pintype "input"))
      (node (ref "U3") (pin "P20") (pinfunction "PS_DDR_A12_502_P20") (pintype "output"))
      (node (ref "U4") (pin "N7") (pinfunction "A12/~{BC}_N7") (pintype "input"))
    )
    (net (code "15") (name "/PS_DDR_A13") (class "Default")
      (node (ref "R22") (pin "1") (pinfunction "1_1") (pintype "passive"))
      (node (ref "U1") (pin "T3") (pinfunction "A13_T3") (pintype "input"))
      (node (ref "U3") (pin "J20") (pinfunction "PS_DDR_A13_502_J20") (pintype "output"))
      (node (ref "U4") (pin "T3") (pinfunction "A13_T3") (pintype "input"))
    )
    (net (code "16") (name "/PS_DDR_A14") (class "Default")
      (node (ref "R23") (pin "1") (pinfunction "1_1") (pintype "passive"))
      (node (ref "U1") (pin "T7") (pinfunction "A14_T7") (pintype "input"))
      (node (ref "U3") (pin "R20") (pinfunction "PS_DDR_A14_502_R20") (pintype "output"))
      (node (ref "U4") (pin "T7") (pinfunction "A14_T7") (pintype "input"))
    )
    (net (code "17") (name "/PS_DDR_BA0") (class "Default")
      (node (ref "R24") (pin "1") (pinfunction "1_1") (pintype "passive"))
      (node (ref "U1") (pin "M2") (pinfunction "BA0_M2") (pintype "input"))
      (node (ref "U3") (pin "U22") (pinfunction "PS_DDR_BA0_502_U22") (pintype "output"))
      (node (ref "U4") (pin "M2") (pinfunction "BA0_M2") (pintype "input"))
    )
    (net (code "18") (name "/PS_DDR_BA1") (class "Default")
      (node (ref "R25") (pin "1") (pinfunction "1_1") (pintype "passive"))
      (node (ref "U1") (pin "N8") (pinfunction "BA1_N8") (pintype "input"))
      (node (ref "U3") (pin "T22") (pinfunction "PS_DDR_BA1_502_T22") (pintype "output"))
      (node (ref "U4") (pin "N8") (pinfunction "BA1_N8") (pintype "input"))
    )
    (net (code "19") (name "/PS_DDR_BA2") (class "Default")
      (node (ref "R26") (pin "1") (pinfunction "1_1") (pintype "passive"))
      (node (ref "U1") (pin "M3") (pinfunction "BA2_M3") (pintype "input"))
      (node (ref "U3") (pin "R22") (pinfunction "PS_DDR_BA2_502_R22") (pintype "output"))
      (node (ref "U4") (pin "M3") (pinfunction "BA2_M3") (pintype "input"))
    )
    (net (code "20") (name "/PS_DDR_CAS") (class "Default")
      (node (ref "R29") (pin "1") (pinfunction "1_1") (pintype "passive"))
      (node (ref "U1") (pin "K3") (pinfunction "~{CAS}_K3") (pintype "input"))
      (node (ref "U3") (pin "Y23") (pinfunction "PS_DDR_CAS_B_502_Y23") (pintype "output"))
      (node (ref "U4") (pin "K3") (pinfunction "~{CAS}_K3") (pintype "input"))
    )
    (net (code "21") (name "/PS_DDR_CKE") (class "Default")
      (node (ref "R27") (pin "1") (pinfunction "1_1") (pintype "passive"))
      (node (ref "U1") (pin "K9") (pinfunction "CKE_K9") (pintype "input"))
      (node (ref "U3") (pin "U21") (pinfunction "PS_DDR_CKE_502_U21") (pintype "output"))
      (node (ref "U4") (pin "K9") (pinfunction "CKE_K9") (pintype "input"))
    )
    (net (code "22") (name "/PS_DDR_CK_N") (class "Default")
      (node (ref "R7") (pin "2") (pinfunction "2_2") (pintype "passive"))
      (node (ref "U1") (pin "K7") (pinfunction "~{CK}_K7") (pintype "input"))
      (node (ref "U3") (pin "P21") (pinfunction "PS_DDR_CKN_502_P21") (pintype "output"))
      (node (ref "U4") (pin "K7") (pinfunction "~{CK}_K7") (pintype "input"))
    )
    (net (code "23") (name "/PS_DDR_CK_P") (class "Default")
      (node (ref "R7") (pin "1") (pinfunction "1_1") (pintype "passive"))
      (node (ref "U1") (pin "J7") (pinfunction "CK_J7") (pintype "input"))
      (node (ref "U3") (pin "R21") (pinfunction "PS_DDR_CKP_502_R21") (pintype "output"))
      (node (ref "U4") (pin "J7") (pinfunction "CK_J7") (pintype "input"))
    )
    (net (code "24") (name "/PS_DDR_CS") (class "Default")
      (node (ref "R28") (pin "1") (pinfunction "1_1") (pintype "passive"))
      (node (ref "U1") (pin "L2") (pinfunction "~{CS}_L2") (pintype "input"))
      (node (ref "U3") (pin "Y21") (pinfunction "PS_DDR_CS_B_502_Y21") (pintype "output"))
      (node (ref "U4") (pin "L2") (pinfunction "~{CS}_L2") (pintype "input"))
    )
    (net (code "25") (name "/PS_DDR_DM_BYTE0") (class "Default")
      (node (ref "U1") (pin "E7") (pinfunction "LDM_E7") (pintype "input"))
      (node (ref "U3") (pin "G24") (pinfunction "PS_DDR_DM0_502_G24") (pintype "output"))
    )
    (net (code "26") (name "/PS_DDR_DM_BYTE1") (class "Default")
      (node (ref "U1") (pin "D3") (pinfunction "UDM_D3") (pintype "input"))
      (node (ref "U3") (pin "K25") (pinfunction "PS_DDR_DM1_502_K25") (pintype "output"))
    )
    (net (code "27") (name "/PS_DDR_DM_BYTE2") (class "Default")
      (node (ref "U3") (pin "P26") (pinfunction "PS_DDR_DM2_502_P26") (pintype "output"))
      (node (ref "U4") (pin "E7") (pinfunction "LDM_E7") (pintype "input"))
    )
    (net (code "28") (name "/PS_DDR_DM_BYTE3") (class "Default")
      (node (ref "U3") (pin "V26") (pinfunction "PS_DDR_DM3_502_V26") (pintype "output"))
      (node (ref "U4") (pin "D3") (pinfunction "UDM_D3") (pintype "input"))
    )
    (net (code "29") (name "/PS_DDR_DQ0") (class "Default")
      (node (ref "U1") (pin "E3") (pinfunction "DQ0_E3") (pintype "bidirectional"))
      (node (ref "U3") (pin "J26") (pinfunction "PS_DDR_DQ0_502_J26") (pintype "bidirectional"))
    )
    (net (code "30") (name "/PS_DDR_DQ1") (class "Default")
      (node (ref "U1") (pin "F7") (pinfunction "DQ1_F7") (pintype "bidirectional"))
      (node (ref "U3") (pin "F25") (pinfunction "PS_DDR_DQ1_502_F25") (pintype "bidirectional"))
    )
    (net (code "31") (name "/PS_DDR_DQ2") (class "Default")
      (node (ref "U1") (pin "F2") (pinfunction "DQ2_F2") (pintype "bidirectional"))
      (node (ref "U3") (pin "J25") (pinfunction "PS_DDR_DQ2_502_J25") (pintype "bidirectional"))
    )
    (net (code "32") (name "/PS_DDR_DQ3") (class "Default")
      (node (ref "U1") (pin "F8") (pinfunction "DQ3_F8") (pintype "bidirectional"))
      (node (ref "U3") (pin "G26") (pinfunction "PS_DDR_DQ3_502_G26") (pintype "bidirectional"))
    )
    (net (code "33") (name "/PS_DDR_DQ4") (class "Default")
      (node (ref "U1") (pin "H3") (pinfunction "DQ4_H3") (pintype "bidirectional"))
      (node (ref "U3") (pin "H26") (pinfunction "PS_DDR_DQ4_502_H26") (pintype "bidirectional"))
    )
    (net (code "34") (name "/PS_DDR_DQ5") (class "Default")
      (node (ref "U1") (pin "H8") (pinfunction "DQ5_H8") (pintype "bidirectional"))
      (node (ref "U3") (pin "H23") (pinfunction "PS_DDR_DQ5_502_H23") (pintype "bidirectional"))
    )
    (net (code "35") (name "/PS_DDR_DQ6") (class "Default")
      (node (ref "U1") (pin "G2") (pinfunction "DQ6_G2") (pintype "bidirectional"))
      (node (ref "U3") (pin "J24") (pinfunction "PS_DDR_DQ6_502_J24") (pintype "bidirectional"))
    )
    (net (code "36") (name "/PS_DDR_DQ7") (class "Default")
      (node (ref "U1") (pin "H7") (pinfunction "DQ7_H7") (pintype "bidirectional"))
      (node (ref "U3") (pin "J23") (pinfunction "PS_DDR_DQ7_502_J23") (pintype "bidirectional"))
    )
    (net (code "37") (name "/PS_DDR_DQ8") (class "Default")
      (node (ref "U1") (pin "D7") (pinfunction "DQ8_D7") (pintype "bidirectional"))
      (node (ref "U3") (pin "K26") (pinfunction "PS_DDR_DQ8_502_K26") (pintype "bidirectional"))
    )
    (net (code "38") (name "/PS_DDR_DQ9") (class "Default")
      (node (ref "U1") (pin "C3") (pinfunction "DQ9_C3") (pintype "bidirectional"))
      (node (ref "U3") (pin "L23") (pinfunction "PS_DDR_DQ9_502_L23") (pintype "bidirectional"))
    )
    (net (code "39") (name "/PS_DDR_DQ10") (class "Default")
      (node (ref "U1") (pin "C8") (pinfunction "DQ10_C8") (pintype "bidirectional"))
      (node (ref "U3") (pin "M26") (pinfunction "PS_DDR_DQ10_502_M26") (pintype "bidirectional"))
    )
    (net (code "40") (name "/PS_DDR_DQ11") (class "Default")
      (node (ref "U1") (pin "C2") (pinfunction "DQ11_C2") (pintype "bidirectional"))
      (node (ref "U3") (pin "K23") (pinfunction "PS_DDR_DQ11_502_K23") (pintype "bidirectional"))
    )
    (net (code "41") (name "/PS_DDR_DQ12") (class "Default")
      (node (ref "U1") (pin "A7") (pinfunction "DQ12_A7") (pintype "bidirectional"))
      (node (ref "U3") (pin "M25") (pinfunction "PS_DDR_DQ12_502_M25") (pintype "bidirectional"))
    )
    (net (code "42") (name "/PS_DDR_DQ13") (class "Default")
      (node (ref "U1") (pin "A2") (pinfunction "DQ13_A2") (pintype "bidirectional"))
      (node (ref "U3") (pin "N24") (pinfunction "PS_DDR_DQ13_502_N24") (pintype "bidirectional"))
    )
    (net (code "43") (name "/PS_DDR_DQ14") (class "Default")
      (node (ref "U1") (pin "B8") (pinfunction "DQ14_B8") (pintype "bidirectional"))
      (node (ref "U3") (pin "M24") (pinfunction "PS_DDR_DQ14_502_M24") (pintype "bidirectional"))
    )
    (net (code "44") (name "/PS_DDR_DQ15") (class "Default")
      (node (ref "U1") (pin "A3") (pinfunction "DQ15_A3") (pintype "bidirectional"))
      (node (ref "U3") (pin "N23") (pinfunction "PS_DDR_DQ15_502_N23") (pintype "bidirectional"))
    )
    (net (code "45") (name "/PS_DDR_DQ16") (class "Default")
      (node (ref "U3") (pin "R26") (pinfunction "PS_DDR_DQ16_502_R26") (pintype "bidirectional"))
      (node (ref "U4") (pin "E3") (pinfunction "DQ0_E3") (pintype "bidirectional"))
    )
    (net (code "46") (name "/PS_DDR_DQ17") (class "Default")
      (node (ref "U3") (pin "P24") (pinfunction "PS_DDR_DQ17_502_P24") (pintype "bidirectional"))
      (node (ref "U4") (pin "F7") (pinfunction "DQ1_F7") (pintype "bidirectional"))
    )
    (net (code "47") (name "/PS_DDR_DQ18") (class "Default")
      (node (ref "U3") (pin "N26") (pinfunction "PS_DDR_DQ18_502_N26") (pintype "bidirectional"))
      (node (ref "U4") (pin "F2") (pinfunction "DQ2_F2") (pintype "bidirectional"))
    )
    (net (code "48") (name "/PS_DDR_DQ19") (class "Default")
      (node (ref "U3") (pin "P23") (pinfunction "PS_DDR_DQ19_502_P23") (pintype "bidirectional"))
      (node (ref "U4") (pin "F8") (pinfunction "DQ3_F8") (pintype "bidirectional"))
    )
    (net (code "49") (name "/PS_DDR_DQ20") (class "Default")
      (node (ref "U3") (pin "T24") (pinfunction "PS_DDR_DQ20_502_T24") (pintype "bidirectional"))
      (node (ref "U4") (pin "H3") (pinfunction "DQ4_H3") (pintype "bidirectional"))
    )
    (net (code "50") (name "/PS_DDR_DQ21") (class "Default")
      (node (ref "U3") (pin "T25") (pinfunction "PS_DDR_DQ21_502_T25") (pintype "bidirectional"))
      (node (ref "U4") (pin "H8") (pinfunction "DQ5_H8") (pintype "bidirectional"))
    )
    (net (code "51") (name "/PS_DDR_DQ22") (class "Default")
      (node (ref "U3") (pin "T23") (pinfunction "PS_DDR_DQ22_502_T23") (pintype "bidirectional"))
      (node (ref "U4") (pin "G2") (pinfunction "DQ6_G2") (pintype "bidirectional"))
    )
    (net (code "52") (name "/PS_DDR_DQ23") (class "Default")
      (node (ref "U3") (pin "R23") (pinfunction "PS_DDR_DQ23_502_R23") (pintype "bidirectional"))
      (node (ref "U4") (pin "H7") (pinfunction "DQ7_H7") (pintype "bidirectional"))
    )
    (net (code "53") (name "/PS_DDR_DQ24") (class "Default")
      (node (ref "U3") (pin "V24") (pinfunction "PS_DDR_DQ24_502_V24") (pintype "bidirectional"))
      (node (ref "U4") (pin "D7") (pinfunction "DQ8_D7") (pintype "bidirectional"))
    )
    (net (code "54") (name "/PS_DDR_DQ25") (class "Default")
      (node (ref "U3") (pin "U26") (pinfunction "PS_DDR_DQ25_502_U26") (pintype "bidirectional"))
      (node (ref "U4") (pin "C3") (pinfunction "DQ9_C3") (pintype "bidirectional"))
    )
    (net (code "55") (name "/PS_DDR_DQ26") (class "Default")
      (node (ref "U3") (pin "U24") (pinfunction "PS_DDR_DQ26_502_U24") (pintype "bidirectional"))
      (node (ref "U4") (pin "C8") (pinfunction "DQ10_C8") (pintype "bidirectional"))
    )
    (net (code "56") (name "/PS_DDR_DQ27") (class "Default")
      (node (ref "U3") (pin "U25") (pinfunction "PS_DDR_DQ27_502_U25") (pintype "bidirectional"))
      (node (ref "U4") (pin "C2") (pinfunction "DQ11_C2") (pintype "bidirectional"))
    )
    (net (code "57") (name "/PS_DDR_DQ28") (class "Default")
      (node (ref "U3") (pin "W26") (pinfunction "PS_DDR_DQ28_502_W26") (pintype "bidirectional"))
      (node (ref "U4") (pin "A7") (pinfunction "DQ12_A7") (pintype "bidirectional"))
    )
    (net (code "58") (name "/PS_DDR_DQ29") (class "Default")
      (node (ref "U3") (pin "Y25") (pinfunction "PS_DDR_DQ29_502_Y25") (pintype "bidirectional"))
      (node (ref "U4") (pin "A2") (pinfunction "DQ13_A2") (pintype "bidirectional"))
    )
    (net (code "59") (name "/PS_DDR_DQ30") (class "Default")
      (node (ref "U3") (pin "Y26") (pinfunction "PS_DDR_DQ30_502_Y26") (pintype "bidirectional"))
      (node (ref "U4") (pin "B8") (pinfunction "DQ14_B8") (pintype "bidirectional"))
    )
    (net (code "60") (name "/PS_DDR_DQ31") (class "Default")
      (node (ref "U3") (pin "W23") (pinfunction "PS_DDR_DQ31_502_W23") (pintype "bidirectional"))
      (node (ref "U4") (pin "A3") (pinfunction "DQ15_A3") (pintype "bidirectional"))
    )
    (net (code "61") (name "/PS_DDR_DQS_BYTE0_N") (class "Default")
      (node (ref "U1") (pin "G3") (pinfunction "~{LDQS}_G3") (pintype "bidirectional"))
      (node (ref "U3") (pin "G25") (pinfunction "PS_DDR_DQS_N0_502_G25") (pintype "bidirectional"))
    )
    (net (code "62") (name "/PS_DDR_DQS_BYTE0_P") (class "Default")
      (node (ref "U1") (pin "F3") (pinfunction "LDQS_F3") (pintype "bidirectional"))
      (node (ref "U3") (pin "H24") (pinfunction "PS_DDR_DQS_P0_502_H24") (pintype "bidirectional"))
    )
    (net (code "63") (name "/PS_DDR_DQS_BYTE1_N") (class "Default")
      (node (ref "U1") (pin "B7") (pinfunction "~{UDQS}_B7") (pintype "bidirectional"))
      (node (ref "U3") (pin "L25") (pinfunction "PS_DDR_DQS_N1_502_L25") (pintype "bidirectional"))
    )
    (net (code "64") (name "/PS_DDR_DQS_BYTE1_P") (class "Default")
      (node (ref "U1") (pin "C7") (pinfunction "UDQS_C7") (pintype "bidirectional"))
      (node (ref "U3") (pin "L24") (pinfunction "PS_DDR_DQS_P1_502_L24") (pintype "bidirectional"))
    )
    (net (code "65") (name "/PS_DDR_DQS_BYTE2_N") (class "Default")
      (node (ref "U3") (pin "R25") (pinfunction "PS_DDR_DQS_N2_502_R25") (pintype "bidirectional"))
      (node (ref "U4") (pin "G3") (pinfunction "~{LDQS}_G3") (pintype "bidirectional"))
    )
    (net (code "66") (name "/PS_DDR_DQS_BYTE2_P") (class "Default")
      (node (ref "U3") (pin "P25") (pinfunction "PS_DDR_DQS_P2_502_P25") (pintype "bidirectional"))
      (node (ref "U4") (pin "F3") (pinfunction "LDQS_F3") (pintype "bidirectional"))
    )
    (net (code "67") (name "/PS_DDR_DQS_BYTE3_N") (class "Default")
      (node (ref "U3") (pin "W25") (pinfunction "PS_DDR_DQS_N3_502_W25") (pintype "bidirectional"))
      (node (ref "U4") (pin "B7") (pinfunction "~{UDQS}_B7") (pintype "bidirectional"))
    )
    (net (code "68") (name "/PS_DDR_DQS_BYTE3_P") (class "Default")
      (node (ref "U3") (pin "W24") (pinfunction "PS_DDR_DQS_P3_502_W24") (pintype "bidirectional"))
      (node (ref "U4") (pin "C7") (pinfunction "UDQS_C7") (pintype "bidirectional"))
    )
    (net (code "69") (name "/PS_DDR_ODT") (class "Default")
      (node (ref "R32") (pin "1") (pinfunction "1_1") (pintype "passive"))
      (node (ref "U1") (pin "K1") (pinfunction "ODT_K1") (pintype "input"))
      (node (ref "U3") (pin "Y22") (pinfunction "PS_DDR_ODT_502_Y22") (pintype "output"))
      (node (ref "U4") (pin "K1") (pinfunction "ODT_K1") (pintype "input"))
    )
    (net (code "70") (name "/PS_DDR_RAS") (class "Default")
      (node (ref "R30") (pin "1") (pinfunction "1_1") (pintype "passive"))
      (node (ref "U1") (pin "J3") (pinfunction "~{RAS}_J3") (pintype "input"))
      (node (ref "U3") (pin "V23") (pinfunction "PS_DDR_RAS_B_502_V23") (pintype "output"))
      (node (ref "U4") (pin "J3") (pinfunction "~{RAS}_J3") (pintype "input"))
    )
    (net (code "71") (name "/PS_DDR_RST") (class "Default")
      (node (ref "R4") (pin "1") (pinfunction "1_1") (pintype "passive"))
      (node (ref "U1") (pin "T2") (pinfunction "~{RESET}_T2") (pintype "input"))
      (node (ref "U3") (pin "H22") (pinfunction "PS_DDR_DRST_B_502_H22") (pintype "output"))
      (node (ref "U4") (pin "T2") (pinfunction "~{RESET}_T2") (pintype "input"))
    )
    (net (code "72") (name "/PS_DDR_WE") (class "Default")
      (node (ref "R31") (pin "1") (pinfunction "1_1") (pintype "passive"))
      (node (ref "U1") (pin "L3") (pinfunction "~{WE}_L3") (pintype "input"))
      (node (ref "U3") (pin "V22") (pinfunction "PS_DDR_WE_B_502_V22") (pintype "output"))
      (node (ref "U4") (pin "L3") (pinfunction "~{WE}_L3") (pintype "input"))
    )
    (net (code "73") (name "2.5V") (class "Default")
      (node (ref "C2") (pin "2") (pinfunction "2_2") (pintype "passive"))
      (node (ref "U2") (pin "10") (pinfunction "VIN_10") (pintype "passive"))
    )
    (net (code "74") (name "GND") (class "Default")
      (node (ref "C1") (pin "1") (pinfunction "1_1") (pintype "passive"))
      (node (ref "C10") (pin "1") (pinfunction "1_1") (pintype "passive"))
      (node (ref "C11") (pin "1") (pinfunction "1_1") (pintype "passive"))
      (node (ref "C12") (pin "1") (pinfunction "1_1") (pintype "passive"))
      (node (ref "C13") (pin "1") (pinfunction "1_1") (pintype "passive"))
      (node (ref "C14") (pin "1") (pinfunction "1_1") (pintype "passive"))
      (node (ref "C15") (pin "1") (pinfunction "1_1") (pintype "passive"))
      (node (ref "C16") (pin "1") (pinfunction "1_1") (pintype "passive"))
      (node (ref "C17") (pin "1") (pinfunction "1_1") (pintype "passive"))
      (node (ref "C18") (pin "1") (pinfunction "1_1") (pintype "passive"))
      (node (ref "C19") (pin "1") (pinfunction "1_1") (pintype "passive"))
      (node (ref "C2") (pin "1") (pinfunction "1_1") (pintype "passive"))
      (node (ref "C20") (pin "1") (pinfunction "1_1") (pintype "passive"))
      (node (ref "C21") (pin "1") (pinfunction "1_1") (pintype "passive"))
      (node (ref "C22") (pin "1") (pinfunction "1_1") (pintype "passive"))
      (node (ref "C23") (pin "1") (pinfunction "1_1") (pintype "passive"))
      (node (ref "C24") (pin "1") (pinfunction "1_1") (pintype "passive"))
      (node (ref "C25") (pin "1") (pinfunction "1_1") (pintype "passive"))
      (node (ref "C26") (pin "1") (pinfunction "1_1") (pintype "passive"))
      (node (ref "C27") (pin "1") (pinfunction "1_1") (pintype "passive"))
      (node (ref "C28") (pin "1") (pinfunction "1_1") (pintype "passive"))
      (node (ref "C29") (pin "1") (pinfunction "1_1") (pintype "passive"))
      (node (ref "C3") (pin "1") (pinfunction "1_1") (pintype "passive"))
      (node (ref "C30") (pin "1") (pinfunction "1_1") (pintype "passive"))
      (node (ref "C31") (pin "1") (pinfunction "1_1") (pintype "passive"))
      (node (ref "C32") (pin "1") (pinfunction "1_1") (pintype "passive"))
      (node (ref "C4") (pin "1") (pinfunction "1_1") (pintype "passive"))
      (node (ref "C5") (pin "1") (pinfunction "1_1") (pintype "passive"))
      (node (ref "C6") (pin "1") (pinfunction "1_1") (pintype "passive"))
      (node (ref "C7") (pin "1") (pinfunction "1_1") (pintype "passive"))
      (node (ref "C8") (pin "1") (pinfunction "1_1") (pintype "passive"))
      (node (ref "C9") (pin "1") (pinfunction "1_1") (pintype "passive"))
      (node (ref "R18") (pin "2") (pinfunction "2_2") (pintype "passive"))
      (node (ref "R2") (pin "1") (pinfunction "1_1") (pintype "passive"))
      (node (ref "R3") (pin "2") (pinfunction "2_2") (pintype "passive"))
      (node (ref "R4") (pin "2") (pinfunction "2_2") (pintype "passive"))
      (node (ref "R5") (pin "1") (pinfunction "1_1") (pintype "passive"))
      (node (ref "U1") (pin "A9") (pinfunction "VSS_A9") (pintype "power_in"))
      (node (ref "U1") (pin "B1") (pinfunction "VSSQ_B1") (pintype "power_in"))
      (node (ref "U1") (pin "B3") (pinfunction "VSS_B3") (pintype "power_in"))
      (node (ref "U1") (pin "B9") (pinfunction "VSSQ_B9") (pintype "power_in"))
      (node (ref "U1") (pin "D1") (pinfunction "VSSQ_D1") (pintype "power_in"))
      (node (ref "U1") (pin "D8") (pinfunction "VSSQ_D8") (pintype "power_in"))
      (node (ref "U1") (pin "E1") (pinfunction "VSS_E1") (pintype "power_in"))
      (node (ref "U1") (pin "E2") (pinfunction "VSSQ_E2") (pintype "power_in"))
      (node (ref "U1") (pin "E8") (pinfunction "VSSQ_E8") (pintype "power_in"))
      (node (ref "U1") (pin "F9") (pinfunction "VSSQ_F9") (pintype "power_in"))
      (node (ref "U1") (pin "G1") (pinfunction "VSSQ_G1") (pintype "power_in"))
      (node (ref "U1") (pin "G8") (pinfunction "VSS_G8") (pintype "power_in"))
      (node (ref "U1") (pin "G9") (pinfunction "VSSQ_G9") (pintype "power_in"))
      (node (ref "U1") (pin "J2") (pinfunction "VSS_J2") (pintype "power_in"))
      (node (ref "U1") (pin "J8") (pinfunction "VSS_J8") (pintype "power_in"))
      (node (ref "U1") (pin "M1") (pinfunction "VSS_M1") (pintype "power_in"))
      (node (ref "U1") (pin "M9") (pinfunction "VSS_M9") (pintype "power_in"))
      (node (ref "U1") (pin "P1") (pinfunction "VSS_P1") (pintype "power_in"))
      (node (ref "U1") (pin "P9") (pinfunction "VSS_P9") (pintype "power_in"))
      (node (ref "U1") (pin "T1") (pinfunction "VSS_T1") (pintype "power_in"))
      (node (ref "U1") (pin "T9") (pinfunction "VSS_T9") (pintype "power_in"))
      (node (ref "U2") (pin "4") (pinfunction "PGND_4") (pintype "power_in"))
      (node (ref "U2") (pin "8") (pinfunction "GND_8") (pintype "power_in"))
      (node (ref "U4") (pin "A9") (pinfunction "VSS_A9") (pintype "power_in"))
      (node (ref "U4") (pin "B1") (pinfunction "VSSQ_B1") (pintype "power_in"))
      (node (ref "U4") (pin "B3") (pinfunction "VSS_B3") (pintype "power_in"))
      (node (ref "U4") (pin "B9") (pinfunction "VSSQ_B9") (pintype "power_in"))
      (node (ref "U4") (pin "D1") (pinfunction "VSSQ_D1") (pintype "power_in"))
      (node (ref "U4") (pin "D8") (pinfunction "VSSQ_D8") (pintype "power_in"))
      (node (ref "U4") (pin "E1") (pinfunction "VSS_E1") (pintype "power_in"))
      (node (ref "U4") (pin "E2") (pinfunction "VSSQ_E2") (pintype "power_in"))
      (node (ref "U4") (pin "E8") (pinfunction "VSSQ_E8") (pintype "power_in"))
      (node (ref "U4") (pin "F9") (pinfunction "VSSQ_F9") (pintype "power_in"))
      (node (ref "U4") (pin "G1") (pinfunction "VSSQ_G1") (pintype "power_in"))
      (node (ref "U4") (pin "G8") (pinfunction "VSS_G8") (pintype "power_in"))
      (node (ref "U4") (pin "G9") (pinfunction "VSSQ_G9") (pintype "power_in"))
      (node (ref "U4") (pin "J2") (pinfunction "VSS_J2") (pintype "power_in"))
      (node (ref "U4") (pin "J8") (pinfunction "VSS_J8") (pintype "power_in"))
      (node (ref "U4") (pin "M1") (pinfunction "VSS_M1") (pintype "power_in"))
      (node (ref "U4") (pin "M9") (pinfunction "VSS_M9") (pintype "power_in"))
      (node (ref "U4") (pin "P1") (pinfunction "VSS_P1") (pintype "power_in"))
      (node (ref "U4") (pin "P9") (pinfunction "VSS_P9") (pintype "power_in"))
      (node (ref "U4") (pin "T1") (pinfunction "VSS_T1") (pintype "power_in"))
      (node (ref "U4") (pin "T9") (pinfunction "VSS_T9") (pintype "power_in"))
    )
    (net (code "75") (name "Net-(U1A-ZQ)") (class "Default")
      (node (ref "R3") (pin "1") (pinfunction "1_1") (pintype "passive"))
      (node (ref "U1") (pin "L8") (pinfunction "ZQ_L8") (pintype "passive"))
    )
    (net (code "76") (name "Net-(U2-VLDOIN)") (class "Default")
      (node (ref "C1") (pin "2") (pinfunction "2_2") (pintype "passive"))
      (node (ref "R1") (pin "1") (pinfunction "1_1") (pintype "passive"))
      (node (ref "R2") (pin "2") (pinfunction "2_2") (pintype "passive"))
      (node (ref "U2") (pin "2") (pinfunction "VLDOIN_2") (pintype "passive"))
    )
    (net (code "77") (name "Net-(U3H-PS_DDR_VRN_502)") (class "Default")
      (node (ref "R6") (pin "2") (pinfunction "2_2") (pintype "passive"))
      (node (ref "U3") (pin "V21") (pinfunction "PS_DDR_VRN_502_V21") (pintype "output"))
    )
    (net (code "78") (name "Net-(U3H-PS_DDR_VRP_502)") (class "Default")
      (node (ref "R5") (pin "2") (pinfunction "2_2") (pintype "passive"))
      (node (ref "U3") (pin "W21") (pinfunction "PS_DDR_VRP_502_W21") (pintype "output"))
    )
    (net (code "79") (name "Net-(U4A-ZQ)") (class "Default")
      (node (ref "R18") (pin "1") (pinfunction "1_1") (pintype "passive"))
      (node (ref "U4") (pin "L8") (pinfunction "ZQ_L8") (pintype "passive"))
    )
    (net (code "80") (name "VCCO_DDR") (class "Default")
      (node (ref "C11") (pin "2") (pinfunction "2_2") (pintype "passive"))
      (node (ref "C12") (pin "2") (pinfunction "2_2") (pintype "passive"))
      (node (ref "C13") (pin "2") (pinfunction "2_2") (pintype "passive"))
      (node (ref "C14") (pin "2") (pinfunction "2_2") (pintype "passive"))
      (node (ref "C15") (pin "2") (pinfunction "2_2") (pintype "passive"))
      (node (ref "C16") (pin "2") (pinfunction "2_2") (pintype "passive"))
      (node (ref "C17") (pin "2") (pinfunction "2_2") (pintype "passive"))
      (node (ref "C18") (pin "2") (pinfunction "2_2") (pintype "passive"))
      (node (ref "C19") (pin "2") (pinfunction "2_2") (pintype "passive"))
      (node (ref "C20") (pin "2") (pinfunction "2_2") (pintype "passive"))
      (node (ref "C21") (pin "2") (pinfunction "2_2") (pintype "passive"))
      (node (ref "C22") (pin "2") (pinfunction "2_2") (pintype "passive"))
      (node (ref "C23") (pin "2") (pinfunction "2_2") (pintype "passive"))
      (node (ref "C24") (pin "2") (pinfunction "2_2") (pintype "passive"))
      (node (ref "C25") (pin "2") (pinfunction "2_2") (pintype "passive"))
      (node (ref "C26") (pin "2") (pinfunction "2_2") (pintype "passive"))
      (node (ref "C27") (pin "2") (pinfunction "2_2") (pintype "passive"))
      (node (ref "C28") (pin "2") (pinfunction "2_2") (pintype "passive"))
      (node (ref "C29") (pin "2") (pinfunction "2_2") (pintype "passive"))
      (node (ref "C3") (pin "2") (pinfunction "2_2") (pintype "passive"))
      (node (ref "C30") (pin "2") (pinfunction "2_2") (pintype "passive"))
      (node (ref "C4") (pin "2") (pinfunction "2_2") (pintype "passive"))
      (node (ref "R1") (pin "2") (pinfunction "2_2") (pintype "passive"))
      (node (ref "R6") (pin "1") (pinfunction "1_1") (pintype "passive"))
      (node (ref "U1") (pin "A1") (pinfunction "VDDQ_A1") (pintype "power_in"))
      (node (ref "U1") (pin "A8") (pinfunction "VDDQ_A8") (pintype "power_in"))
      (node (ref "U1") (pin "B2") (pinfunction "VDD_B2") (pintype "power_in"))
      (node (ref "U1") (pin "C1") (pinfunction "VDDQ_C1") (pintype "power_in"))
      (node (ref "U1") (pin "C9") (pinfunction "VDDQ_C9") (pintype "power_in"))
      (node (ref "U1") (pin "D2") (pinfunction "VDDQ_D2") (pintype "power_in"))
      (node (ref "U1") (pin "D9") (pinfunction "VDD_D9") (pintype "power_in"))
      (node (ref "U1") (pin "E9") (pinfunction "VDDQ_E9") (pintype "power_in"))
      (node (ref "U1") (pin "F1") (pinfunction "VDDQ_F1") (pintype "power_in"))
      (node (ref "U1") (pin "G7") (pinfunction "VDD_G7") (pintype "power_in"))
      (node (ref "U1") (pin "H2") (pinfunction "VDDQ_H2") (pintype "power_in"))
      (node (ref "U1") (pin "H9") (pinfunction "VDDQ_H9") (pintype "power_in"))
      (node (ref "U1") (pin "K2") (pinfunction "VDD_K2") (pintype "power_in"))
      (node (ref "U1") (pin "K8") (pinfunction "VDD_K8") (pintype "power_in"))
      (node (ref "U1") (pin "N1") (pinfunction "VDD_N1") (pintype "power_in"))
      (node (ref "U1") (pin "N9") (pinfunction "VDD_N9") (pintype "power_in"))
      (node (ref "U1") (pin "R1") (pinfunction "VDD_R1") (pintype "power_in"))
      (node (ref "U1") (pin "R9") (pinfunction "VDD_R9") (pintype "power_in"))
      (node (ref "U2") (pin "1") (pinfunction "REFIN_1") (pintype "passive"))
      (node (ref "U4") (pin "A1") (pinfunction "VDDQ_A1") (pintype "power_in"))
      (node (ref "U4") (pin "A8") (pinfunction "VDDQ_A8") (pintype "power_in"))
      (node (ref "U4") (pin "B2") (pinfunction "VDD_B2") (pintype "power_in"))
      (node (ref "U4") (pin "C1") (pinfunction "VDDQ_C1") (pintype "power_in"))
      (node (ref "U4") (pin "C9") (pinfunction "VDDQ_C9") (pintype "power_in"))
      (node (ref "U4") (pin "D2") (pinfunction "VDDQ_D2") (pintype "power_in"))
      (node (ref "U4") (pin "D9") (pinfunction "VDD_D9") (pintype "power_in"))
      (node (ref "U4") (pin "E9") (pinfunction "VDDQ_E9") (pintype "power_in"))
      (node (ref "U4") (pin "F1") (pinfunction "VDDQ_F1") (pintype "power_in"))
      (node (ref "U4") (pin "G7") (pinfunction "VDD_G7") (pintype "power_in"))
      (node (ref "U4") (pin "H2") (pinfunction "VDDQ_H2") (pintype "power_in"))
      (node (ref "U4") (pin "H9") (pinfunction "VDDQ_H9") (pintype "power_in"))
      (node (ref "U4") (pin "K2") (pinfunction "VDD_K2") (pintype "power_in"))
      (node (ref "U4") (pin "K8") (pinfunction "VDD_K8") (pintype "power_in"))
      (node (ref "U4") (pin "N1") (pinfunction "VDD_N1") (pintype "power_in"))
      (node (ref "U4") (pin "N9") (pinfunction "VDD_N9") (pintype "power_in"))
      (node (ref "U4") (pin "R1") (pinfunction "VDD_R1") (pintype "power_in"))
      (node (ref "U4") (pin "R9") (pinfunction "VDD_R9") (pintype "power_in"))
    )
    (net (code "81") (name "VTT_DDR") (class "Default")
      (node (ref "C5") (pin "2") (pinfunction "2_2") (pintype "passive"))
      (node (ref "C6") (pin "2") (pinfunction "2_2") (pintype "passive"))
      (node (ref "C7") (pin "2") (pinfunction "2_2") (pintype "passive"))
      (node (ref "R10") (pin "2") (pinfunction "2_2") (pintype "passive"))
      (node (ref "R11") (pin "2") (pinfunction "2_2") (pintype "passive"))
      (node (ref "R12") (pin "2") (pinfunction "2_2") (pintype "passive"))
      (node (ref "R13") (pin "2") (pinfunction "2_2") (pintype "passive"))
      (node (ref "R14") (pin "2") (pinfunction "2_2") (pintype "passive"))
      (node (ref "R15") (pin "2") (pinfunction "2_2") (pintype "passive"))
      (node (ref "R16") (pin "2") (pinfunction "2_2") (pintype "passive"))
      (node (ref "R17") (pin "2") (pinfunction "2_2") (pintype "passive"))
      (node (ref "R19") (pin "2") (pinfunction "2_2") (pintype "passive"))
      (node (ref "R20") (pin "2") (pinfunction "2_2") (pintype "passive"))
      (node (ref "R21") (pin "2") (pinfunction "2_2") (pintype "passive"))
      (node (ref "R22") (pin "2") (pinfunction "2_2") (pintype "passive"))
      (node (ref "R23") (pin "2") (pinfunction "2_2") (pintype "passive"))
      (node (ref "R24") (pin "2") (pinfunction "2_2") (pintype "passive"))
      (node (ref "R25") (pin "2") (pinfunction "2_2") (pintype "passive"))
      (node (ref "R26") (pin "2") (pinfunction "2_2") (pintype "passive"))
      (node (ref "R27") (pin "2") (pinfunction "2_2") (pintype "passive"))
      (node (ref "R28") (pin "2") (pinfunction "2_2") (pintype "passive"))
      (node (ref "R29") (pin "2") (pinfunction "2_2") (pintype "passive"))
      (node (ref "R30") (pin "2") (pinfunction "2_2") (pintype "passive"))
      (node (ref "R31") (pin "2") (pinfunction "2_2") (pintype "passive"))
      (node (ref "R32") (pin "2") (pinfunction "2_2") (pintype "passive"))
      (node (ref "R8") (pin "2") (pinfunction "2_2") (pintype "passive"))
      (node (ref "R9") (pin "2") (pinfunction "2_2") (pintype "passive"))
      (node (ref "U2") (pin "3") (pinfunction "VO_3") (pintype "passive"))
      (node (ref "U2") (pin "5") (pinfunction "VOSNS_5") (pintype "passive"))
    )
    (net (code "82") (name "VTT_REF") (class "Default")
      (node (ref "C10") (pin "2") (pinfunction "2_2") (pintype "passive"))
      (node (ref "C31") (pin "2") (pinfunction "2_2") (pintype "passive"))
      (node (ref "C32") (pin "2") (pinfunction "2_2") (pintype "passive"))
      (node (ref "C8") (pin "2") (pinfunction "2_2") (pintype "passive"))
      (node (ref "C9") (pin "2") (pinfunction "2_2") (pintype "passive"))
      (node (ref "U1") (pin "H1") (pinfunction "VREFDQ_H1") (pintype "power_in"))
      (node (ref "U1") (pin "M8") (pinfunction "VREFCA_M8") (pintype "power_in"))
      (node (ref "U2") (pin "6") (pinfunction "REFOUT_6") (pintype "passive"))
      (node (ref "U3") (pin "K21") (pinfunction "PS_DDR_VREF0_502_K21") (pintype "input"))
      (node (ref "U3") (pin "M21") (pinfunction "PS_DDR_VREF1_502_M21") (pintype "input"))
      (node (ref "U4") (pin "H1") (pinfunction "VREFDQ_H1") (pintype "power_in"))
      (node (ref "U4") (pin "M8") (pinfunction "VREFCA_M8") (pintype "power_in"))
    )
    (net (code "83") (name "unconnected-(U1A-NC-PadJ1)") (class "Default")
      (node (ref "U1") (pin "J1") (pinfunction "NC_J1") (pintype "passive+no_connect"))
    )
    (net (code "84") (name "unconnected-(U1A-NC-PadJ9)") (class "Default")
      (node (ref "U1") (pin "J9") (pinfunction "NC_J9") (pintype "passive+no_connect"))
    )
    (net (code "85") (name "unconnected-(U1A-NC-PadL1)") (class "Default")
      (node (ref "U1") (pin "L1") (pinfunction "NC_L1") (pintype "passive+no_connect"))
    )
    (net (code "86") (name "unconnected-(U1A-NC-PadL9)") (class "Default")
      (node (ref "U1") (pin "L9") (pinfunction "NC_L9") (pintype "passive+no_connect"))
    )
    (net (code "87") (name "unconnected-(U1A-NC-PadM7)") (class "Default")
      (node (ref "U1") (pin "M7") (pinfunction "NC_M7") (pintype "passive+no_connect"))
    )
    (net (code "88") (name "unconnected-(U2-EP-Pad11)") (class "Default")
      (node (ref "U2") (pin "11") (pinfunction "EP_11") (pintype "bidirectional"))
    )
    (net (code "89") (name "unconnected-(U2-PGOOD-Pad9)") (class "Default")
      (node (ref "U2") (pin "9") (pinfunction "PGOOD_9") (pintype "output+no_connect"))
    )
    (net (code "90") (name "unconnected-(U4A-NC-PadJ1)") (class "Default")
      (node (ref "U4") (pin "J1") (pinfunction "NC_J1") (pintype "passive+no_connect"))
    )
    (net (code "91") (name "unconnected-(U4A-NC-PadJ9)") (class "Default")
      (node (ref "U4") (pin "J9") (pinfunction "NC_J9") (pintype "passive+no_connect"))
    )
    (net (code "92") (name "unconnected-(U4A-NC-PadL1)") (class "Default")
      (node (ref "U4") (pin "L1") (pinfunction "NC_L1") (pintype "passive+no_connect"))
    )
    (net (code "93") (name "unconnected-(U4A-NC-PadL9)") (class "Default")
      (node (ref "U4") (pin "L9") (pinfunction "NC_L9") (pintype "passive+no_connect"))
    )
    (net (code "94") (name "unconnected-(U4A-NC-PadM7)") (class "Default")
      (node (ref "U4") (pin "M7") (pinfunction "NC_M7") (pintype "passive+no_connect"))
    )
  )
)
